# RHButtonBoard.net
KiCad netlist of a schematic drawn in EAGLE
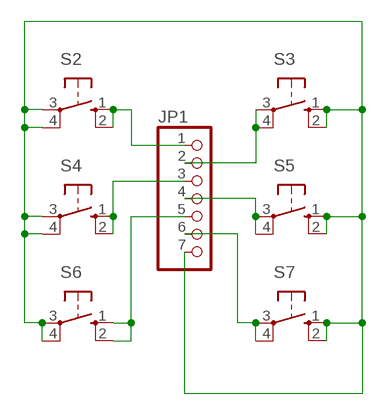
[diagram p0: schematic, sheet 1]

(export (version "E")
  (design (tool "Eeschema 10.0.6"))
  (components
    (comp (ref "JP1")
      (value "PINHD-1X7")
      (footprint "eagle-import:1X07")
      (libsource (lib "eagle-import") (part "PINHD-1X7"))
    )
    (comp (ref "S2")
      (value "10-XX")
      (footprint "eagle-import:B3F-10XX")
      (fields (field (name "MPN") "B3F-1000"))
      (libsource (lib "eagle-import") (part "10-XX"))
    )
    (comp (ref "S3")
      (value "10-XX")
      (footprint "eagle-import:B3F-10XX")
      (fields (field (name "MPN") "B3F-1000"))
      (libsource (lib "eagle-import") (part "10-XX"))
    )
    (comp (ref "S4")
      (value "10-XX")
      (footprint "eagle-import:B3F-10XX")
      (fields (field (name "MPN") "B3F-1000"))
      (libsource (lib "eagle-import") (part "10-XX"))
    )
    (comp (ref "S5")
      (value "10-XX")
      (footprint "eagle-import:B3F-10XX")
      (fields (field (name "MPN") "B3F-1000"))
      (libsource (lib "eagle-import") (part "10-XX"))
    )
    (comp (ref "S6")
      (value "10-XX")
      (footprint "eagle-import:B3F-10XX")
      (fields (field (name "MPN") "B3F-1000"))
      (libsource (lib "eagle-import") (part "10-XX"))
    )
    (comp (ref "S7")
      (value "10-XX")
      (footprint "eagle-import:B3F-10XX")
      (fields (field (name "MPN") "B3F-1000"))
      (libsource (lib "eagle-import") (part "10-XX"))
    )
  )
  (nets
    (net (code "1") (name "Net-(S2-P)") (class "Default")
      (node (ref "JP1") (pin "7") (pinfunction "7_7") (pintype "passive"))
      (node (ref "S2") (pin "3") (pinfunction "P_3") (pintype "passive"))
      (node (ref "S2") (pin "4") (pinfunction "P1_4") (pintype "passive"))
      (node (ref "S3") (pin "1") (pinfunction "S_1") (pintype "passive"))
      (node (ref "S3") (pin "2") (pinfunction "S1_2") (pintype "passive"))
      (node (ref "S4") (pin "3") (pinfunction "P_3") (pintype "passive"))
      (node (ref "S4") (pin "4") (pinfunction "P1_4") (pintype "passive"))
      (node (ref "S5") (pin "1") (pinfunction "S_1") (pintype "passive"))
      (node (ref "S5") (pin "2") (pinfunction "S1_2") (pintype "passive"))
      (node (ref "S6") (pin "3") (pinfunction "P_3") (pintype "passive"))
      (node (ref "S6") (pin "4") (pinfunction "P1_4") (pintype "passive"))
      (node (ref "S7") (pin "1") (pinfunction "S_1") (pintype "passive"))
      (node (ref "S7") (pin "2") (pinfunction "S1_2") (pintype "passive"))
    )
    (net (code "2") (name "Net-(S2-S)") (class "Default")
      (node (ref "JP1") (pin "1") (pinfunction "1_1") (pintype "passive"))
      (node (ref "S2") (pin "1") (pinfunction "S_1") (pintype "passive"))
      (node (ref "S2") (pin "2") (pinfunction "S1_2") (pintype "passive"))
    )
    (net (code "3") (name "Net-(S3-P)") (class "Default")
      (node (ref "JP1") (pin "2") (pinfunction "2_2") (pintype "passive"))
      (node (ref "S3") (pin "3") (pinfunction "P_3") (pintype "passive"))
      (node (ref "S3") (pin "4") (pinfunction "P1_4") (pintype "passive"))
    )
    (net (code "4") (name "Net-(S4-S)") (class "Default")
      (node (ref "JP1") (pin "3") (pinfunction "3_3") (pintype "passive"))
      (node (ref "S4") (pin "1") (pinfunction "S_1") (pintype "passive"))
      (node (ref "S4") (pin "2") (pinfunction "S1_2") (pintype "passive"))
    )
    (net (code "5") (name "Net-(S5-P)") (class "Default")
      (node (ref "JP1") (pin "4") (pinfunction "4_4") (pintype "passive"))
      (node (ref "S5") (pin "3") (pinfunction "P_3") (pintype "passive"))
      (node (ref "S5") (pin "4") (pinfunction "P1_4") (pintype "passive"))
    )
    (net (code "6") (name "Net-(S6-S)") (class "Default")
      (node (ref "JP1") (pin "5") (pinfunction "5_5") (pintype "passive"))
      (node (ref "S6") (pin "1") (pinfunction "S_1") (pintype "passive"))
      (node (ref "S6") (pin "2") (pinfunction "S1_2") (pintype "passive"))
    )
    (net (code "7") (name "Net-(S7-P)") (class "Default")
      (node (ref "JP1") (pin "6") (pinfunction "6_6") (pintype "passive"))
      (node (ref "S7") (pin "3") (pinfunction "P_3") (pintype "passive"))
      (node (ref "S7") (pin "4") (pinfunction "P1_4") (pintype "passive"))
    )
  )
)
